# demo_dermis_main_testboard_back.net
KiCad netlist of a schematic drawn in Altium Designer
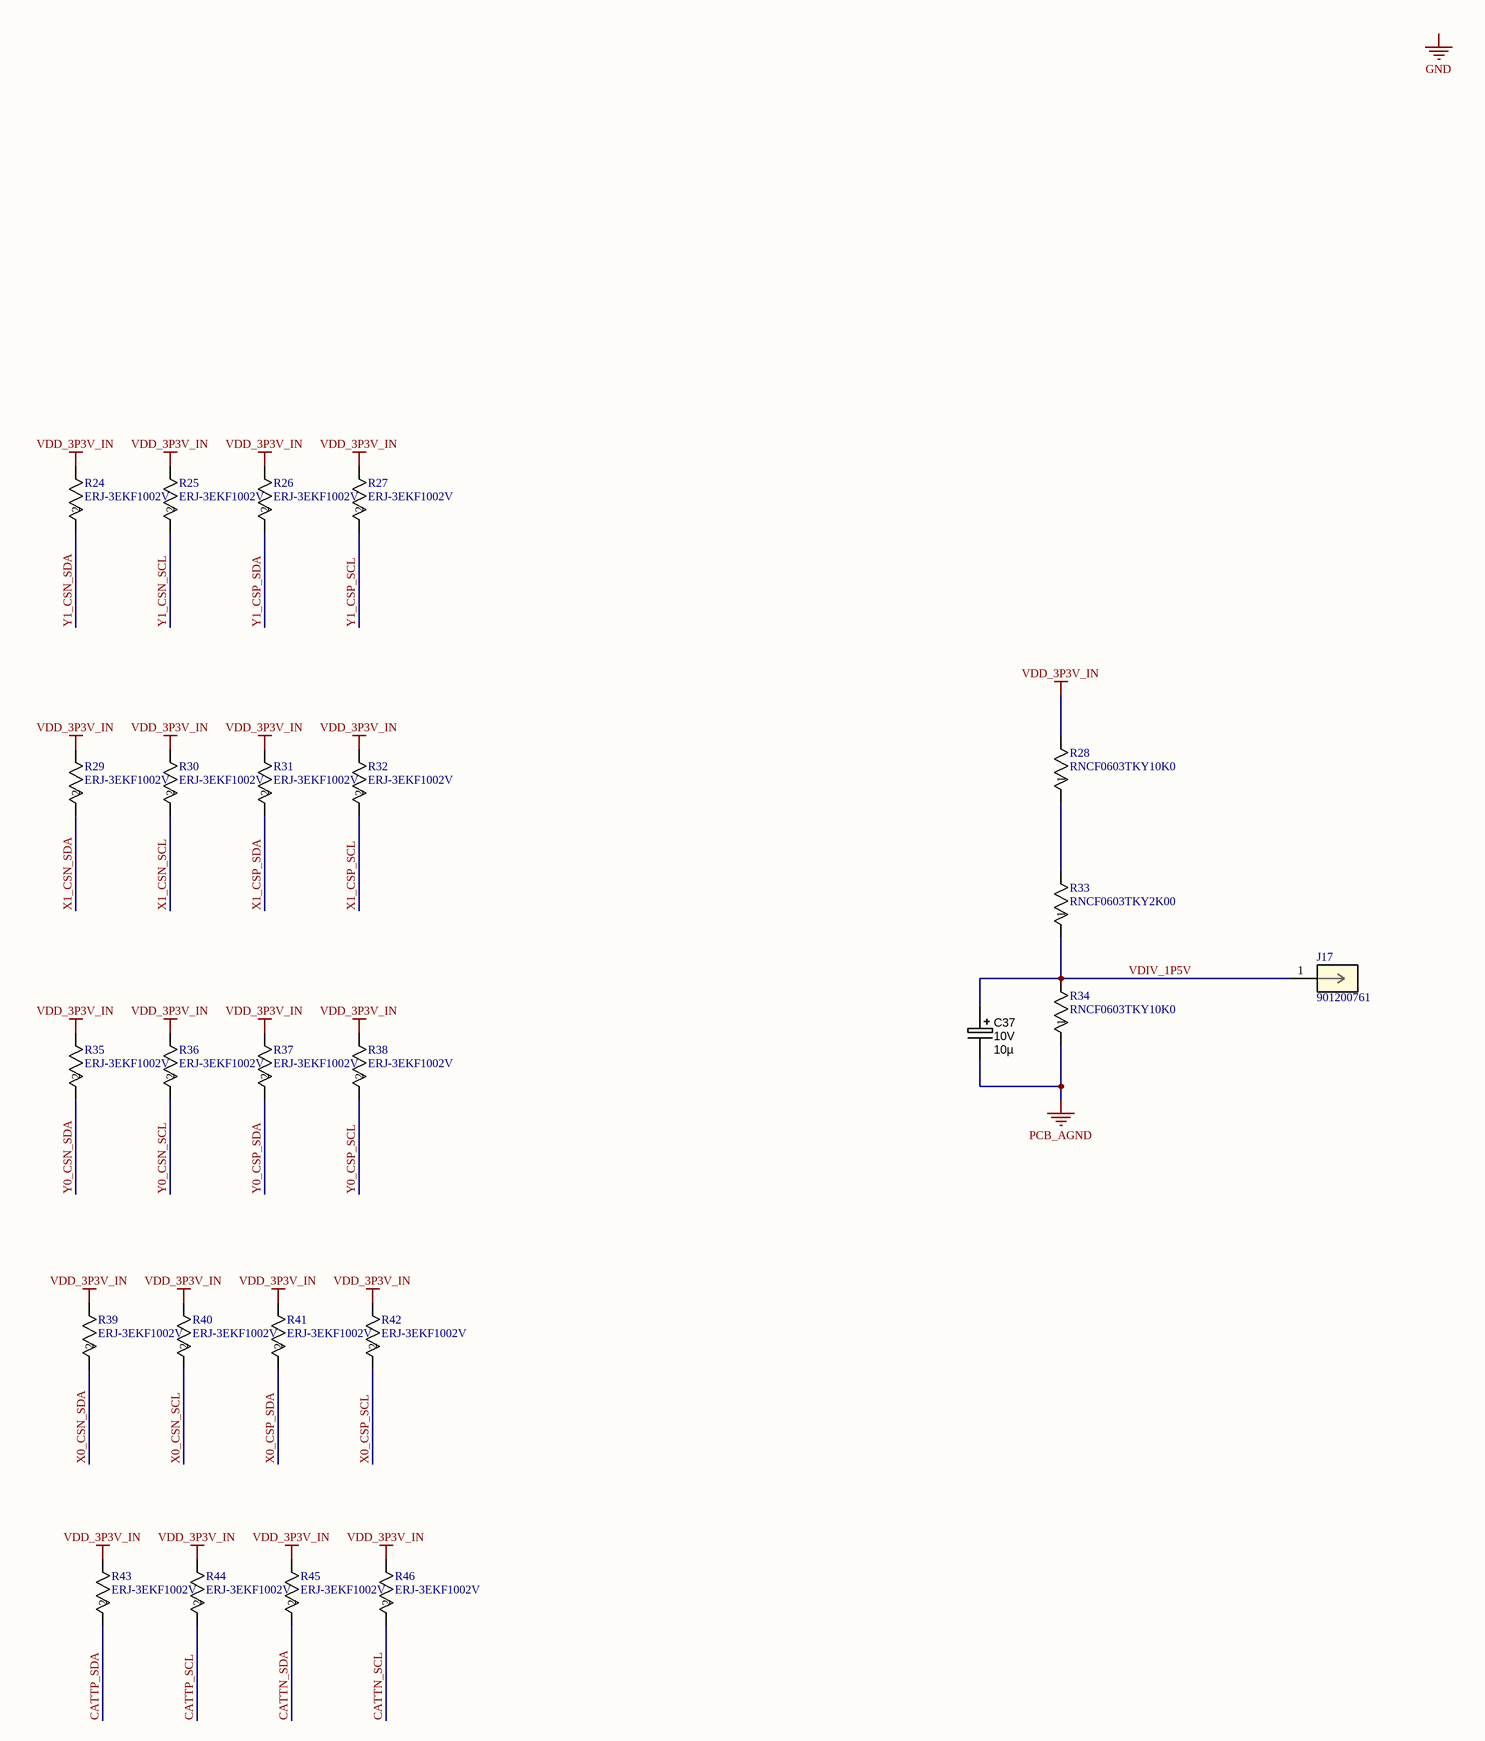
[diagram p0: demo_dermis_main_testboard_back.SchDoc]

(export (version "E")
  (design (tool "Eeschema 10.0.6"))
  (components
    (comp (ref "C37")
      (value "10µ")
      (footprint "CAPMP2012X150USR")
      (description "Capacitor SMD Tantalum 10uF 20% 10V 0805")
      (fields (field (name "TOLERANCE") "±20%") (field (name "RATINGS") "10V"))
      (libsource (lib "PBL - Capacitors") (part "CAPT_10u_0805_10V"))
    )
    (comp (ref "J17")
      (value "901200761")
      (footprint "CONN_90120-0761_MOL")
      (description "No Description Available")
      (fields (field (name "COPYRIGHT") "Copyright (C) 2022 Ultra Librarian. All rights reserved."))
      (libsource (lib "901200761") (part "901200761"))
    )
    (comp (ref "R24")
      (value "ERJ-3EKF1002V")
      (footprint "RC0603N_PAN")
      (description "No Description Available")
      (libsource (lib "ERJ-3EKF1002V") (part "ERJ-3EKF1002V"))
    )
    (comp (ref "R25")
      (value "ERJ-3EKF1002V")
      (footprint "RC0603N_PAN")
      (description "No Description Available")
      (libsource (lib "ERJ-3EKF1002V") (part "ERJ-3EKF1002V"))
    )
    (comp (ref "R26")
      (value "ERJ-3EKF1002V")
      (footprint "RC0603N_PAN")
      (description "No Description Available")
      (libsource (lib "ERJ-3EKF1002V") (part "ERJ-3EKF1002V"))
    )
    (comp (ref "R27")
      (value "ERJ-3EKF1002V")
      (footprint "RC0603N_PAN")
      (description "No Description Available")
      (libsource (lib "ERJ-3EKF1002V") (part "ERJ-3EKF1002V"))
    )
    (comp (ref "R28")
      (value "RNCF0603TKY10K0")
      (footprint "STA_RNCF0603_STP")
      (description "No Description Available")
      (libsource (lib "RNCF0603TKY10K0") (part "RNCF0603TKY10K0"))
    )
    (comp (ref "R29")
      (value "ERJ-3EKF1002V")
      (footprint "RC0603N_PAN")
      (description "No Description Available")
      (libsource (lib "ERJ-3EKF1002V") (part "ERJ-3EKF1002V"))
    )
    (comp (ref "R30")
      (value "ERJ-3EKF1002V")
      (footprint "RC0603N_PAN")
      (description "No Description Available")
      (libsource (lib "ERJ-3EKF1002V") (part "ERJ-3EKF1002V"))
    )
    (comp (ref "R31")
      (value "ERJ-3EKF1002V")
      (footprint "RC0603N_PAN")
      (description "No Description Available")
      (libsource (lib "ERJ-3EKF1002V") (part "ERJ-3EKF1002V"))
    )
    (comp (ref "R32")
      (value "ERJ-3EKF1002V")
      (footprint "RC0603N_PAN")
      (description "No Description Available")
      (libsource (lib "ERJ-3EKF1002V") (part "ERJ-3EKF1002V"))
    )
    (comp (ref "R33")
      (value "RNCF0603TKY2K00")
      (footprint "RES_RNCF0603_STP")
      (description "No Description Available")
      (libsource (lib "RNCF0603TKY2K00") (part "RNCF0603TKY2K00"))
    )
    (comp (ref "R34")
      (value "RNCF0603TKY10K0")
      (footprint "STA_RNCF0603_STP")
      (description "No Description Available")
      (libsource (lib "RNCF0603TKY10K0") (part "RNCF0603TKY10K0"))
    )
    (comp (ref "R35")
      (value "ERJ-3EKF1002V")
      (footprint "RC0603N_PAN")
      (description "No Description Available")
      (libsource (lib "ERJ-3EKF1002V") (part "ERJ-3EKF1002V"))
    )
    (comp (ref "R36")
      (value "ERJ-3EKF1002V")
      (footprint "RC0603N_PAN")
      (description "No Description Available")
      (libsource (lib "ERJ-3EKF1002V") (part "ERJ-3EKF1002V"))
    )
    (comp (ref "R37")
      (value "ERJ-3EKF1002V")
      (footprint "RC0603N_PAN")
      (description "No Description Available")
      (libsource (lib "ERJ-3EKF1002V") (part "ERJ-3EKF1002V"))
    )
    (comp (ref "R38")
      (value "ERJ-3EKF1002V")
      (footprint "RC0603N_PAN")
      (description "No Description Available")
      (libsource (lib "ERJ-3EKF1002V") (part "ERJ-3EKF1002V"))
    )
    (comp (ref "R39")
      (value "ERJ-3EKF1002V")
      (footprint "RC0603N_PAN")
      (description "No Description Available")
      (libsource (lib "ERJ-3EKF1002V") (part "ERJ-3EKF1002V"))
    )
    (comp (ref "R40")
      (value "ERJ-3EKF1002V")
      (footprint "RC0603N_PAN")
      (description "No Description Available")
      (libsource (lib "ERJ-3EKF1002V") (part "ERJ-3EKF1002V"))
    )
    (comp (ref "R41")
      (value "ERJ-3EKF1002V")
      (footprint "RC0603N_PAN")
      (description "No Description Available")
      (libsource (lib "ERJ-3EKF1002V") (part "ERJ-3EKF1002V"))
    )
    (comp (ref "R42")
      (value "ERJ-3EKF1002V")
      (footprint "RC0603N_PAN")
      (description "No Description Available")
      (libsource (lib "ERJ-3EKF1002V") (part "ERJ-3EKF1002V"))
    )
    (comp (ref "R43")
      (value "ERJ-3EKF1002V")
      (footprint "RC0603N_PAN")
      (description "No Description Available")
      (libsource (lib "ERJ-3EKF1002V") (part "ERJ-3EKF1002V"))
    )
    (comp (ref "R44")
      (value "ERJ-3EKF1002V")
      (footprint "RC0603N_PAN")
      (description "No Description Available")
      (libsource (lib "ERJ-3EKF1002V") (part "ERJ-3EKF1002V"))
    )
    (comp (ref "R45")
      (value "ERJ-3EKF1002V")
      (footprint "RC0603N_PAN")
      (description "No Description Available")
      (libsource (lib "ERJ-3EKF1002V") (part "ERJ-3EKF1002V"))
    )
    (comp (ref "R46")
      (value "ERJ-3EKF1002V")
      (footprint "RC0603N_PAN")
      (description "No Description Available")
      (libsource (lib "ERJ-3EKF1002V") (part "ERJ-3EKF1002V"))
    )
  )
  (nets
    (net (code "1") (name "/CATTN_SCL") (class "Default")
      (node (ref "R46") (pin "2") (pinfunction "2_2") (pintype "passive"))
    )
    (net (code "2") (name "/CATTN_SDA") (class "Default")
      (node (ref "R45") (pin "2") (pinfunction "2_2") (pintype "passive"))
    )
    (net (code "3") (name "/CATTP_SCL") (class "Default")
      (node (ref "R44") (pin "2") (pinfunction "2_2") (pintype "passive"))
    )
    (net (code "4") (name "/CATTP_SDA") (class "Default")
      (node (ref "R43") (pin "2") (pinfunction "2_2") (pintype "passive"))
    )
    (net (code "5") (name "/VDIV_1P5V") (class "Default")
      (node (ref "C37") (pin "1") (pintype "passive"))
      (node (ref "J17") (pin "1") (pinfunction "1_1") (pintype "passive"))
      (node (ref "R33") (pin "1") (pinfunction "1_1") (pintype "passive"))
      (node (ref "R34") (pin "2") (pinfunction "2_2") (pintype "passive"))
    )
    (net (code "6") (name "/X0_CSN_SCL") (class "Default")
      (node (ref "R40") (pin "2") (pinfunction "2_2") (pintype "passive"))
    )
    (net (code "7") (name "/X0_CSN_SDA") (class "Default")
      (node (ref "R39") (pin "2") (pinfunction "2_2") (pintype "passive"))
    )
    (net (code "8") (name "/X0_CSP_SCL") (class "Default")
      (node (ref "R42") (pin "2") (pinfunction "2_2") (pintype "passive"))
    )
    (net (code "9") (name "/X0_CSP_SDA") (class "Default")
      (node (ref "R41") (pin "2") (pinfunction "2_2") (pintype "passive"))
    )
    (net (code "10") (name "/X1_CSN_SCL") (class "Default")
      (node (ref "R30") (pin "2") (pinfunction "2_2") (pintype "passive"))
    )
    (net (code "11") (name "/X1_CSN_SDA") (class "Default")
      (node (ref "R29") (pin "2") (pinfunction "2_2") (pintype "passive"))
    )
    (net (code "12") (name "/X1_CSP_SCL") (class "Default")
      (node (ref "R32") (pin "2") (pinfunction "2_2") (pintype "passive"))
    )
    (net (code "13") (name "/X1_CSP_SDA") (class "Default")
      (node (ref "R31") (pin "2") (pinfunction "2_2") (pintype "passive"))
    )
    (net (code "14") (name "/Y0_CSN_SCL") (class "Default")
      (node (ref "R36") (pin "2") (pinfunction "2_2") (pintype "passive"))
    )
    (net (code "15") (name "/Y0_CSN_SDA") (class "Default")
      (node (ref "R35") (pin "2") (pinfunction "2_2") (pintype "passive"))
    )
    (net (code "16") (name "/Y0_CSP_SCL") (class "Default")
      (node (ref "R38") (pin "2") (pinfunction "2_2") (pintype "passive"))
    )
    (net (code "17") (name "/Y0_CSP_SDA") (class "Default")
      (node (ref "R37") (pin "2") (pinfunction "2_2") (pintype "passive"))
    )
    (net (code "18") (name "/Y1_CSN_SCL") (class "Default")
      (node (ref "R25") (pin "2") (pinfunction "2_2") (pintype "passive"))
    )
    (net (code "19") (name "/Y1_CSN_SDA") (class "Default")
      (node (ref "R24") (pin "2") (pinfunction "2_2") (pintype "passive"))
    )
    (net (code "20") (name "/Y1_CSP_SCL") (class "Default")
      (node (ref "R27") (pin "2") (pinfunction "2_2") (pintype "passive"))
    )
    (net (code "21") (name "/Y1_CSP_SDA") (class "Default")
      (node (ref "R26") (pin "2") (pinfunction "2_2") (pintype "passive"))
    )
    (net (code "23") (name "Net-(R28-Pad1)") (class "Default")
      (node (ref "R28") (pin "1") (pinfunction "1_1") (pintype "passive"))
      (node (ref "R33") (pin "2") (pinfunction "2_2") (pintype "passive"))
    )
    (net (code "24") (name "PCB_AGND") (class "Default")
      (node (ref "C37") (pin "2") (pintype "passive"))
      (node (ref "R34") (pin "1") (pinfunction "1_1") (pintype "passive"))
    )
    (net (code "25") (name "VDD_3P3V_IN") (class "Default")
      (node (ref "R24") (pin "1") (pinfunction "1_1") (pintype "passive"))
      (node (ref "R25") (pin "1") (pinfunction "1_1") (pintype "passive"))
      (node (ref "R26") (pin "1") (pinfunction "1_1") (pintype "passive"))
      (node (ref "R27") (pin "1") (pinfunction "1_1") (pintype "passive"))
      (node (ref "R28") (pin "2") (pinfunction "2_2") (pintype "passive"))
      (node (ref "R29") (pin "1") (pinfunction "1_1") (pintype "passive"))
      (node (ref "R30") (pin "1") (pinfunction "1_1") (pintype "passive"))
      (node (ref "R31") (pin "1") (pinfunction "1_1") (pintype "passive"))
      (node (ref "R32") (pin "1") (pinfunction "1_1") (pintype "passive"))
      (node (ref "R35") (pin "1") (pinfunction "1_1") (pintype "passive"))
      (node (ref "R36") (pin "1") (pinfunction "1_1") (pintype "passive"))
      (node (ref "R37") (pin "1") (pinfunction "1_1") (pintype "passive"))
      (node (ref "R38") (pin "1") (pinfunction "1_1") (pintype "passive"))
      (node (ref "R39") (pin "1") (pinfunction "1_1") (pintype "passive"))
      (node (ref "R40") (pin "1") (pinfunction "1_1") (pintype "passive"))
      (node (ref "R41") (pin "1") (pinfunction "1_1") (pintype "passive"))
      (node (ref "R42") (pin "1") (pinfunction "1_1") (pintype "passive"))
      (node (ref "R43") (pin "1") (pinfunction "1_1") (pintype "passive"))
      (node (ref "R44") (pin "1") (pinfunction "1_1") (pintype "passive"))
      (node (ref "R45") (pin "1") (pinfunction "1_1") (pintype "passive"))
      (node (ref "R46") (pin "1") (pinfunction "1_1") (pintype "passive"))
    )
  )
)
